# 03_-_MCU_and_Conn.net
KiCad netlist of a schematic drawn in Altium Designer
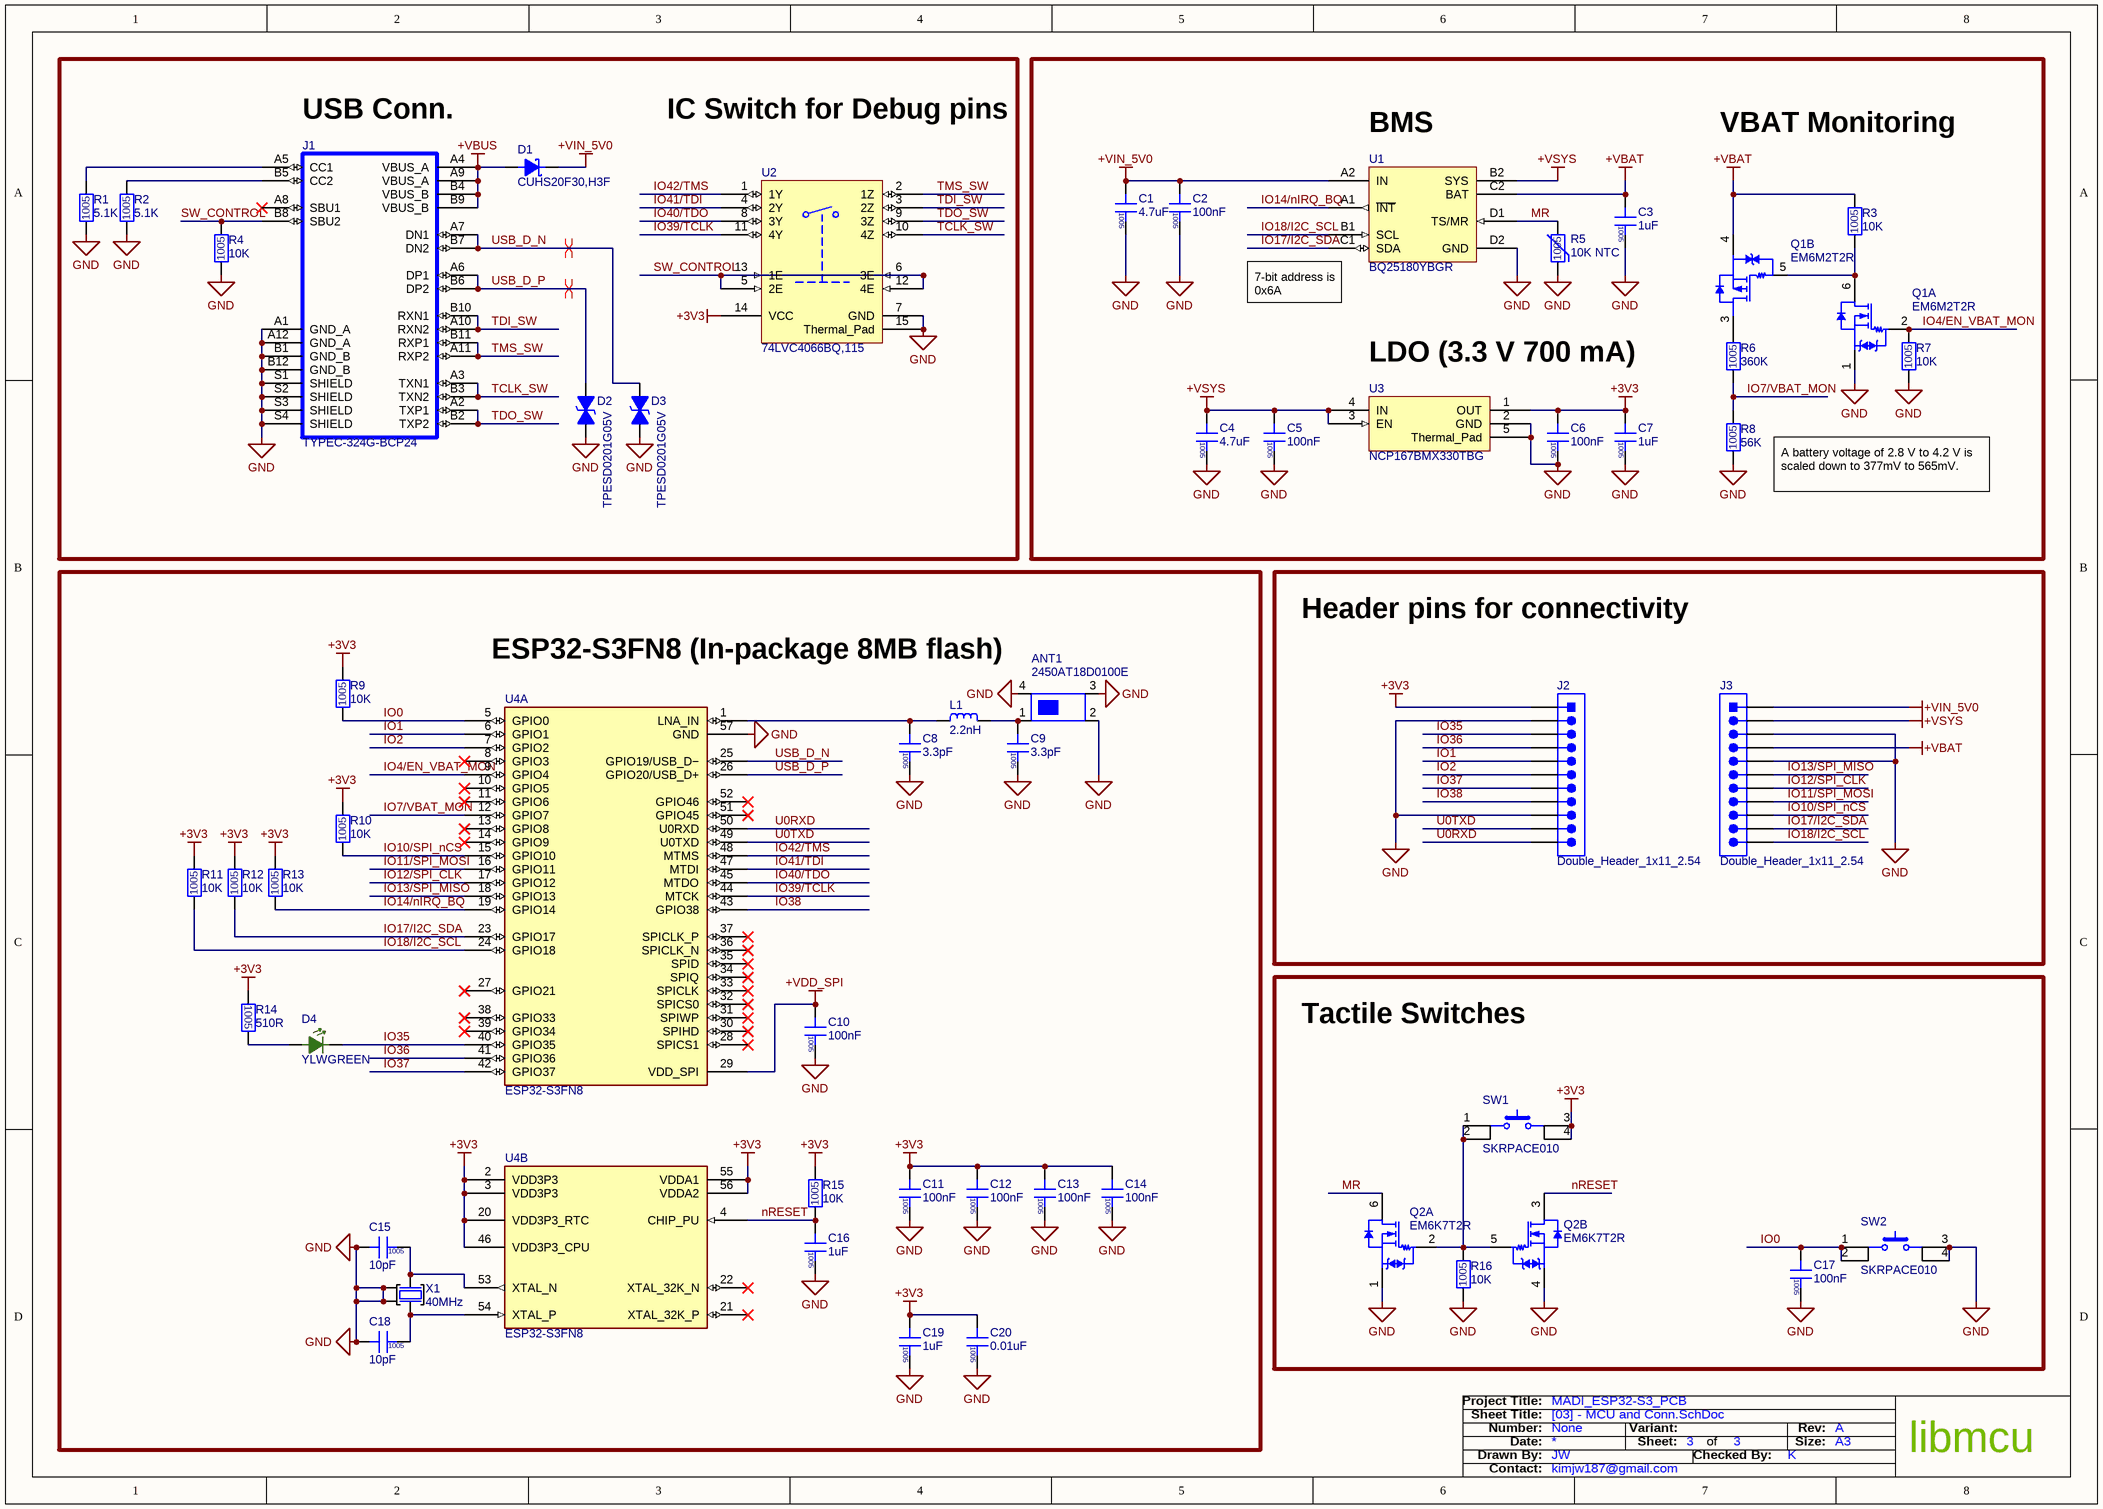
[diagram p0: [03] - MCU and Conn.SchDoc]

(export (version "E")
  (design (tool "Eeschema 10.0.6"))
  (components
    (comp (ref "ANT1")
      (value "2450AT18D0100E")
      (footprint "2450AT18D0100E")
      (description "RF ANT 2.4GHZ CHIP SOLDER SMD")
      (fields (field (name "MANUFACTURER") "Johanson"))
      (libsource (lib "Schlib-master") (part "2450AT18D0100E"))
    )
    (comp (ref "C1")
      (value "4.7uF")
      (footprint "CAPC1005X06N")
      (description "CAP CER 4.7UF 10V X5R 0402")
      (fields
        (field (name "MANUFACTURER") "Samsung")
        (field (name "MANUFACTURER PART NUMBER") "CL05A475MP5NRNC")
      )
      (libsource (lib "Schlib-master") (part "CL05A475MP5NRNC"))
    )
    (comp (ref "C2")
      (value "100nF")
      (footprint "CAPC1005X06N")
      (description "CAP CER 0.1UF 16V X7R 0402")
      (fields
        (field (name "MANUFACTURER") "Samsung")
        (field (name "MANUFACTURER PART NUMBER") "CL05B104KO5NNNC")
      )
      (libsource (lib "Schlib-master") (part "CL05B104KO5NNNC"))
    )
    (comp (ref "C3")
      (value "1uF")
      (footprint "CAPC1005X06N")
      (description "CAP CER 1UF 16V X5R 0402")
      (fields
        (field (name "MANUFACTURER") "Samsung")
        (field (name "MANUFACTURER PART NUMBER") "CL05A105KO5NNNC")
      )
      (libsource (lib "Schlib-master") (part "CL05A105KO5NNNC"))
    )
    (comp (ref "C4")
      (value "4.7uF")
      (footprint "CAPC1005X06N")
      (description "CAP CER 4.7UF 10V X5R 0402")
      (fields
        (field (name "MANUFACTURER") "Samsung")
        (field (name "MANUFACTURER PART NUMBER") "CL05A475MP5NRNC")
      )
      (libsource (lib "Schlib-master") (part "CL05A475MP5NRNC"))
    )
    (comp (ref "C5")
      (value "100nF")
      (footprint "CAPC1005X06N")
      (description "CAP CER 0.1UF 16V X7R 0402")
      (fields
        (field (name "MANUFACTURER") "Samsung")
        (field (name "MANUFACTURER PART NUMBER") "CL05B104KO5NNNC")
      )
      (libsource (lib "Schlib-master") (part "CL05B104KO5NNNC"))
    )
    (comp (ref "C6")
      (value "100nF")
      (footprint "CAPC1005X06N")
      (description "CAP CER 0.1UF 16V X7R 0402")
      (fields
        (field (name "MANUFACTURER") "Samsung")
        (field (name "MANUFACTURER PART NUMBER") "CL05B104KO5NNNC")
      )
      (libsource (lib "Schlib-master") (part "CL05B104KO5NNNC"))
    )
    (comp (ref "C7")
      (value "1uF")
      (footprint "CAPC1005X06N")
      (description "CAP CER 1UF 16V X5R 0402")
      (fields
        (field (name "MANUFACTURER") "Samsung")
        (field (name "MANUFACTURER PART NUMBER") "CL05A105KO5NNNC")
      )
      (libsource (lib "Schlib-master") (part "CL05A105KO5NNNC"))
    )
    (comp (ref "C8")
      (value "3.3pF")
      (footprint "CAPC1005X06N")
      (description "CAP CER 3.3PF 50V C0G/NPO 0402")
      (fields
        (field (name "MANUFACTURER") "Yageo")
        (field (name "MANUFACTURER PART NUMBER") "CC0402CRNPO9BN3R3")
      )
      (libsource (lib "Schlib-master") (part "CC0402CRNPO9BN3R3"))
    )
    (comp (ref "C9")
      (value "3.3pF")
      (footprint "CAPC1005X06N")
      (description "CAP CER 3.3PF 50V C0G/NPO 0402")
      (fields
        (field (name "MANUFACTURER") "Yageo")
        (field (name "MANUFACTURER PART NUMBER") "CC0402CRNPO9BN3R3")
      )
      (libsource (lib "Schlib-master") (part "CC0402CRNPO9BN3R3"))
    )
    (comp (ref "C10")
      (value "100nF")
      (footprint "CAPC1005X06N")
      (description "CAP CER 0.1UF 16V X7R 0402")
      (fields
        (field (name "MANUFACTURER") "Samsung")
        (field (name "MANUFACTURER PART NUMBER") "CL05B104KO5NNNC")
      )
      (libsource (lib "Schlib-master") (part "CL05B104KO5NNNC"))
    )
    (comp (ref "C11")
      (value "100nF")
      (footprint "CAPC1005X06N")
      (description "CAP CER 0.1UF 16V X7R 0402")
      (fields
        (field (name "MANUFACTURER") "Samsung")
        (field (name "MANUFACTURER PART NUMBER") "CL05B104KO5NNNC")
      )
      (libsource (lib "Schlib-master") (part "CL05B104KO5NNNC"))
    )
    (comp (ref "C12")
      (value "100nF")
      (footprint "CAPC1005X06N")
      (description "CAP CER 0.1UF 16V X7R 0402")
      (fields
        (field (name "MANUFACTURER") "Samsung")
        (field (name "MANUFACTURER PART NUMBER") "CL05B104KO5NNNC")
      )
      (libsource (lib "Schlib-master") (part "CL05B104KO5NNNC"))
    )
    (comp (ref "C13")
      (value "100nF")
      (footprint "CAPC1005X06N")
      (description "CAP CER 0.1UF 16V X7R 0402")
      (fields
        (field (name "MANUFACTURER") "Samsung")
        (field (name "MANUFACTURER PART NUMBER") "CL05B104KO5NNNC")
      )
      (libsource (lib "Schlib-master") (part "CL05B104KO5NNNC"))
    )
    (comp (ref "C14")
      (value "100nF")
      (footprint "CAPC1005X06N")
      (description "CAP CER 0.1UF 16V X7R 0402")
      (fields
        (field (name "MANUFACTURER") "Samsung")
        (field (name "MANUFACTURER PART NUMBER") "CL05B104KO5NNNC")
      )
      (libsource (lib "Schlib-master") (part "CL05B104KO5NNNC"))
    )
    (comp (ref "C15")
      (value "10pF")
      (footprint "CAPC1005X06N")
      (description "CAP CER 10PF 50V C0G/NPO 0402")
      (fields
        (field (name "MANUFACTURER") "Yageo")
        (field (name "MANUFACTURER PART NUMBER") "CC0402JRNPO9BN100")
      )
      (libsource (lib "Schlib-master") (part "CC0402JRNPO9BN100"))
    )
    (comp (ref "C16")
      (value "1uF")
      (footprint "CAPC1005X06N")
      (description "CAP CER 1UF 16V X5R 0402")
      (fields
        (field (name "MANUFACTURER") "Samsung")
        (field (name "MANUFACTURER PART NUMBER") "CL05A105KO5NNNC")
      )
      (libsource (lib "Schlib-master") (part "CL05A105KO5NNNC"))
    )
    (comp (ref "C17")
      (value "100nF")
      (footprint "CAPC1005X06N")
      (description "CAP CER 0.1UF 16V X7R 0402")
      (fields
        (field (name "MANUFACTURER") "Samsung")
        (field (name "MANUFACTURER PART NUMBER") "CL05B104KO5NNNC")
      )
      (libsource (lib "Schlib-master") (part "CL05B104KO5NNNC"))
    )
    (comp (ref "C18")
      (value "10pF")
      (footprint "CAPC1005X06N")
      (description "CAP CER 10PF 50V C0G/NPO 0402")
      (fields
        (field (name "MANUFACTURER") "Yageo")
        (field (name "MANUFACTURER PART NUMBER") "CC0402JRNPO9BN100")
      )
      (libsource (lib "Schlib-master") (part "CC0402JRNPO9BN100"))
    )
    (comp (ref "C19")
      (value "1uF")
      (footprint "CAPC1005X06N")
      (description "CAP CER 1UF 16V X5R 0402")
      (fields
        (field (name "MANUFACTURER") "Samsung")
        (field (name "MANUFACTURER PART NUMBER") "CL05A105KO5NNNC")
      )
      (libsource (lib "Schlib-master") (part "CL05A105KO5NNNC"))
    )
    (comp (ref "C20")
      (value "0.01uF")
      (footprint "CAPC1005X06N")
      (description "CAP CER 10000PF 25V X7R 0402")
      (fields
        (field (name "MANUFACTURER") "Samsung")
        (field (name "MANUFACTURER PART NUMBER") "CL05B103KA5NNNC")
      )
      (libsource (lib "Schlib-master") (part "CL05B103KA5NNNC"))
    )
    (comp (ref "D1")
      (value "CUHS20F30,H3F")
      (footprint "US2H-DIODE")
      (description "DIODE SCHOTTKY 30V 2A US2H")
      (fields (field (name "MANUFACTURER") "Toshiba"))
      (libsource (lib "Schlib-master") (part "CUHS20F30,H3F"))
    )
    (comp (ref "D2")
      (value "TPESD0201G05V")
      (footprint "DIOC0603X03N")
      (description "TVS DIODE 5.5VWM 40VC 0201")
      (fields (field (name "MANUFACTURER") "TECH PUBLIC"))
      (libsource (lib "Schlib-master") (part "TPESD0201G05V"))
    )
    (comp (ref "D3")
      (value "TPESD0201G05V")
      (footprint "DIOC0603X03N")
      (description "TVS DIODE 5.5VWM 40VC 0201")
      (fields (field (name "MANUFACTURER") "TECH PUBLIC"))
      (libsource (lib "Schlib-master") (part "TPESD0201G05V"))
    )
    (comp (ref "D4")
      (value "YLWGREEN")
      (footprint "LDIOC1608X08N")
      (description "LED YLW/GREEN DIFFUSED 1608 SMD")
      (fields
        (field (name "MANUFACTURER") "Everlight")
        (field (name "MANUFACTURER PART NUMBER") "19-217/G7C-AN1P2/3T")
      )
      (libsource (lib "Schlib-master") (part "19-217/G7C-AN1P2/3T"))
    )
    (comp (ref "J1")
      (value "TYPEC-324G-BCP24")
      (footprint "KUSBX-SMT3-CS-BTR_KYC")
      (description "CONN RCPT USB TYPE C, SMT PINS, TH SHIELD")
      (fields (field (name "MANUFACTURER") "XUNPU"))
      (libsource (lib "Schlib-master") (part "TYPEC-324G-BCP24"))
    )
    (comp (ref "J2")
      (value "Double_Header_1x11_2.54")
      (footprint "1x11_DOUBLE_HEADER_2.54")
      (libsource (lib "") (part "Double_Header_1x11_2.54_1"))
    )
    (comp (ref "J3")
      (value "Double_Header_1x11_2.54")
      (footprint "1x11_DOUBLE_HEADER_2.54")
      (libsource (lib "Schlib-master") (part "Double_Header_1x11_2.54"))
    )
    (comp (ref "L1")
      (value "2.2nH")
      (footprint "INDC1005X05N")
      (description "FIXED IND 2.2NH 400MA 180 MOHM")
      (fields
        (field (name "MANUFACTURER") "Chilisin Elec")
        (field (name "MANUFACTURER PART NUMBER") "CLH1005T-2N2S-S-NP")
      )
      (libsource (lib "Schlib-master") (part "CLH1005T-2N2S-S-NP"))
    )
    (comp (ref "Q1")
      (value "EM6M2T2R")
      (footprint "SOTFL50P160X55-6N")
      (description "MOSFET N/P-CH 20V 0.2A EMT6")
      (fields (field (name "MANUFACTURER") "Rohm"))
      (libsource (lib "Schlib-master") (part "EM6M2T2R"))
    )
    (comp (ref "Q2")
      (value "EM6K7T2R")
      (footprint "SOTFL50P160X55-6N")
      (description "MOSFET 2N-CH 20V 0.2A EMT6")
      (fields (field (name "MANUFACTURER") "Rohm"))
      (libsource (lib "Schlib-master") (part "EM6K7T2R"))
    )
    (comp (ref "R1")
      (value "5.1K")
      (footprint "RESC1005X04N")
      (description "RES SMD 5.1K OHM 1% 1/16W 0402")
      (fields
        (field (name "MANUFACTURER") "Yageo")
        (field (name "MANUFACTURER PART NUMBER") "RC0402FR-075K1L")
      )
      (libsource (lib "Schlib-master") (part "RC0402FR-075K1L"))
    )
    (comp (ref "R2")
      (value "5.1K")
      (footprint "RESC1005X04N")
      (description "RES SMD 5.1K OHM 1% 1/16W 0402")
      (fields
        (field (name "MANUFACTURER") "Yageo")
        (field (name "MANUFACTURER PART NUMBER") "RC0402FR-075K1L")
      )
      (libsource (lib "Schlib-master") (part "RC0402FR-075K1L"))
    )
    (comp (ref "R3")
      (value "10K")
      (footprint "RESC1005X04N")
      (description "RES SMD 10K OHM 1% 1/16W 0402")
      (fields
        (field (name "MANUFACTURER") "Yageo")
        (field (name "MANUFACTURER PART NUMBER") "RC0402FR-0710KL")
      )
      (libsource (lib "Schlib-master") (part "RC0402FR-0710KL"))
    )
    (comp (ref "R4")
      (value "10K")
      (footprint "RESC1005X04N")
      (description "RES SMD 10K OHM 1% 1/16W 0402")
      (fields
        (field (name "MANUFACTURER") "Yageo")
        (field (name "MANUFACTURER PART NUMBER") "RC0402FR-0710KL")
      )
      (libsource (lib "Schlib-master") (part "RC0402FR-0710KL"))
    )
    (comp (ref "R5")
      (value "10K NTC")
      (footprint "NTC1005X05N")
      (description "THERMISTOR NTC 10KOHM 3380K 0402")
      (fields
        (field (name "MANUFACTURER") "Murata")
        (field (name "MANUFACTURER PART NUMBER") "NCP15XH103F03RC")
      )
      (libsource (lib "Schlib-master") (part "NCP15XH103F03RC"))
    )
    (comp (ref "R6")
      (value "360K")
      (footprint "RESC1005X04N")
      (description "RES SMD 360K OHM 1% 1/16W 0402")
      (fields
        (field (name "MANUFACTURER") "Yageo")
        (field (name "MANUFACTURER PART NUMBER") "RC0402FR-07360KL")
      )
      (libsource (lib "Schlib-master") (part "RC0402FR-07360KL"))
    )
    (comp (ref "R7")
      (value "10K")
      (footprint "RESC1005X04N")
      (description "RES SMD 10K OHM 1% 1/16W 0402")
      (fields
        (field (name "MANUFACTURER") "Yageo")
        (field (name "MANUFACTURER PART NUMBER") "RC0402FR-0710KL")
      )
      (libsource (lib "Schlib-master") (part "RC0402FR-0710KL"))
    )
    (comp (ref "R8")
      (value "56K")
      (footprint "RESC1005X04N")
      (description "RES SMD 56K OHM 1% 1/16W 0402")
      (fields
        (field (name "MANUFACTURER") "Yageo")
        (field (name "MANUFACTURER PART NUMBER") "RC0402FR-0756KL")
      )
      (libsource (lib "Schlib-master") (part "RC0402FR-0756KL"))
    )
    (comp (ref "R9")
      (value "10K")
      (footprint "RESC1005X04N")
      (description "RES SMD 10K OHM 1% 1/16W 0402")
      (fields
        (field (name "MANUFACTURER") "Yageo")
        (field (name "MANUFACTURER PART NUMBER") "RC0402FR-0710KL")
      )
      (libsource (lib "Schlib-master") (part "RC0402FR-0710KL"))
    )
    (comp (ref "R10")
      (value "10K")
      (footprint "RESC1005X04N")
      (description "RES SMD 10K OHM 1% 1/16W 0402")
      (fields
        (field (name "MANUFACTURER") "Yageo")
        (field (name "MANUFACTURER PART NUMBER") "RC0402FR-0710KL")
      )
      (libsource (lib "Schlib-master") (part "RC0402FR-0710KL"))
    )
    (comp (ref "R11")
      (value "10K")
      (footprint "RESC1005X04N")
      (description "RES SMD 10K OHM 1% 1/16W 0402")
      (fields
        (field (name "MANUFACTURER") "Yageo")
        (field (name "MANUFACTURER PART NUMBER") "RC0402FR-0710KL")
      )
      (libsource (lib "Schlib-master") (part "RC0402FR-0710KL"))
    )
    (comp (ref "R12")
      (value "10K")
      (footprint "RESC1005X04N")
      (description "RES SMD 10K OHM 1% 1/16W 0402")
      (fields
        (field (name "MANUFACTURER") "Yageo")
        (field (name "MANUFACTURER PART NUMBER") "RC0402FR-0710KL")
      )
      (libsource (lib "Schlib-master") (part "RC0402FR-0710KL"))
    )
    (comp (ref "R13")
      (value "10K")
      (footprint "RESC1005X04N")
      (description "RES SMD 10K OHM 1% 1/16W 0402")
      (fields
        (field (name "MANUFACTURER") "Yageo")
        (field (name "MANUFACTURER PART NUMBER") "RC0402FR-0710KL")
      )
      (libsource (lib "Schlib-master") (part "RC0402FR-0710KL"))
    )
    (comp (ref "R14")
      (value "510R")
      (footprint "RESC1005X04N")
      (description "RES SMD 510 OHM 1% 1/16W 0402")
      (fields (field (name "TOLERANCE") "1%") (field (name "MANUFACTURER") "Yageo"))
      (libsource (lib "Schlib-master") (part "RC0402FR-07510RL"))
    )
    (comp (ref "R15")
      (value "10K")
      (footprint "RESC1005X04N")
      (description "RES SMD 10K OHM 1% 1/16W 0402")
      (fields
        (field (name "MANUFACTURER") "Yageo")
        (field (name "MANUFACTURER PART NUMBER") "RC0402FR-0710KL")
      )
      (libsource (lib "Schlib-master") (part "RC0402FR-0710KL"))
    )
    (comp (ref "R16")
      (value "10K")
      (footprint "RESC1005X04N")
      (description "RES SMD 10K OHM 1% 1/16W 0402")
      (fields
        (field (name "MANUFACTURER") "Yageo")
        (field (name "MANUFACTURER PART NUMBER") "RC0402FR-0710KL")
      )
      (libsource (lib "Schlib-master") (part "RC0402FR-0710KL"))
    )
    (comp (ref "SW1")
      (value "SKRPACE010")
      (footprint "PTS810")
      (description "SWITCH TACTILE SPST-NO 0.05A 16V")
      (fields (field (name "MANUFACTURER") "Alps Electric"))
      (libsource (lib "Schlib-master") (part "SKRPACE010"))
    )
    (comp (ref "SW2")
      (value "SKRPACE010")
      (footprint "PTS810")
      (description "SWITCH TACTILE SPST-NO 0.05A 16V")
      (fields (field (name "MANUFACTURER") "Alps Electric"))
      (libsource (lib "Schlib-master") (part "SKRPACE010"))
    )
    (comp (ref "U1")
      (value "BQ25180YBGR")
      (footprint "BGA8C40P2X4_100X155X50_YBG0008")
      (description "IC 1-A LI-ION IC PROGRAMMABLE CHARG")
      (fields (field (name "MANUFACTURER") "Texas Instruments"))
      (libsource (lib "Schlib-master") (part "BQ25180YBGR"))
    )
    (comp (ref "U2")
      (value "74LVC4066BQ,115")
      (footprint "QFN50P250X300X100_HS-15N")
      (description "IC SWITCH QUAD SPST 14DHVQFN")
      (fields (field (name "MANUFACTURER") "Nexperia"))
      (libsource (lib "Schlib-master") (part "74LVC4066BQ,115"))
    )
    (comp (ref "U3")
      (value "NCP167BMX330TBG")
      (footprint "NCP167")
      (description "IC REG LINEAR 3.3V 700MA 4XDFN")
      (fields (field (name "MANUFACTURER") "ON Semiconductor"))
      (libsource (lib "Schlib-master") (part "NCP167BMX330TBG"))
    )
    (comp (ref "U4")
      (value "ESP32-S3FN8")
      (footprint "QFN40P700X700X90_HS-57N")
      (description "IC RF TXRX+MCU BLUETOOTH WIFI")
      (fields (field (name "MANUFACTURER") "Espressif Systems"))
      (libsource (lib "Schlib-master") (part "ESP32-S3FN8"))
    )
    (comp (ref "X1")
      (value "40MHz")
      (footprint "XT2016_ECS")
      (description "CRYSTAL 40.0000MHZ 9PF SMD")
      (fields (field (name "MANUFACTURER") "HD") (field (name "MANUFACTURER PART NUMBER") "7D040000H01"))
      (libsource (lib "Schlib-master") (part "7D040000H01"))
    )
  )
  (nets
    (net (code "1") (name "+3V3") (class "Default")
      (node (ref "C11") (pin "2") (pinfunction "2_2") (pintype "passive"))
      (node (ref "C12") (pin "2") (pinfunction "2_2") (pintype "passive"))
      (node (ref "C13") (pin "2") (pinfunction "2_2") (pintype "passive"))
      (node (ref "C14") (pin "2") (pinfunction "2_2") (pintype "passive"))
      (node (ref "C19") (pin "2") (pinfunction "2_2") (pintype "passive"))
      (node (ref "C20") (pin "2") (pinfunction "2_2") (pintype "passive"))
      (node (ref "C6") (pin "2") (pinfunction "2_2") (pintype "passive"))
      (node (ref "C7") (pin "2") (pinfunction "2_2") (pintype "passive"))
      (node (ref "J2") (pin "1") (pinfunction "1_1") (pintype "passive"))
      (node (ref "R10") (pin "2") (pinfunction "2_2") (pintype "passive"))
      (node (ref "R11") (pin "2") (pinfunction "2_2") (pintype "passive"))
      (node (ref "R12") (pin "2") (pinfunction "2_2") (pintype "passive"))
      (node (ref "R13") (pin "2") (pinfunction "2_2") (pintype "passive"))
      (node (ref "R14") (pin "2") (pinfunction "2_2") (pintype "passive"))
      (node (ref "R15") (pin "2") (pinfunction "2_2") (pintype "passive"))
      (node (ref "R9") (pin "2") (pinfunction "2_2") (pintype "passive"))
      (node (ref "SW1") (pin "3") (pinfunction "2_3") (pintype "passive"))
      (node (ref "SW1") (pin "4") (pinfunction "1_4") (pintype "passive"))
      (node (ref "U2") (pin "14") (pinfunction "VCC_14") (pintype "power_in"))
      (node (ref "U3") (pin "1") (pinfunction "OUT_1") (pintype "power_in"))
      (node (ref "U4") (pin "2") (pinfunction "VDD3P3_2") (pintype "power_in"))
      (node (ref "U4") (pin "20") (pinfunction "VDD3P3_RTC_20") (pintype "power_in"))
      (node (ref "U4") (pin "3") (pinfunction "VDD3P3_3") (pintype "power_in"))
      (node (ref "U4") (pin "46") (pinfunction "VDD3P3_CPU_46") (pintype "power_in"))
      (node (ref "U4") (pin "55") (pinfunction "VDDA1_55") (pintype "power_in"))
      (node (ref "U4") (pin "56") (pinfunction "VDDA2_56") (pintype "power_in"))
    )
    (net (code "2") (name "+VBAT") (class "Default")
      (node (ref "C3") (pin "2") (pinfunction "2_2") (pintype "passive"))
      (node (ref "J3") (pin "4") (pinfunction "4_4") (pintype "passive"))
      (node (ref "Q1") (pin "4") (pinfunction "S_4") (pintype "passive"))
      (node (ref "R3") (pin "2") (pinfunction "2_2") (pintype "passive"))
      (node (ref "U1") (pin "C2") (pinfunction "BAT_C2") (pintype "power_in"))
    )
    (net (code "3") (name "+VBUS") (class "Default")
      (node (ref "D1") (pin "2") (pinfunction "Anode_2") (pintype "passive"))
      (node (ref "J1") (pin "A4") (pinfunction "VBUS_A_A4") (pintype "power_in"))
      (node (ref "J1") (pin "A9") (pinfunction "VBUS_A_A9") (pintype "power_in"))
      (node (ref "J1") (pin "B4") (pinfunction "VBUS_B_B4") (pintype "power_in"))
      (node (ref "J1") (pin "B9") (pinfunction "VBUS_B_B9") (pintype "power_in"))
    )
    (net (code "4") (name "+VDD_SPI") (class "Default")
      (node (ref "C10") (pin "2") (pinfunction "2_2") (pintype "passive"))
      (node (ref "U4") (pin "29") (pinfunction "VDD_SPI_29") (pintype "power_in"))
    )
    (net (code "5") (name "+VIN_5V0") (class "Default")
      (node (ref "C1") (pin "2") (pinfunction "2_2") (pintype "passive"))
      (node (ref "C2") (pin "2") (pinfunction "2_2") (pintype "passive"))
      (node (ref "D1") (pin "1") (pinfunction "Cathode_1") (pintype "passive"))
      (node (ref "J3") (pin "1") (pinfunction "1_1") (pintype "passive"))
      (node (ref "U1") (pin "A2") (pinfunction "IN_A2") (pintype "power_in"))
    )
    (net (code "6") (name "+VSYS") (class "Default")
      (node (ref "C4") (pin "2") (pinfunction "2_2") (pintype "passive"))
      (node (ref "C5") (pin "2") (pinfunction "2_2") (pintype "passive"))
      (node (ref "J3") (pin "2") (pinfunction "2_2") (pintype "passive"))
      (node (ref "U1") (pin "B2") (pinfunction "SYS_B2") (pintype "power_in"))
      (node (ref "U3") (pin "3") (pinfunction "EN_3") (pintype "input"))
      (node (ref "U3") (pin "4") (pinfunction "IN_4") (pintype "power_in"))
    )
    (net (code "7") (name "/IO0") (class "Default")
      (node (ref "C17") (pin "2") (pinfunction "2_2") (pintype "passive"))
      (node (ref "R9") (pin "1") (pinfunction "1_1") (pintype "passive"))
      (node (ref "SW2") (pin "1") (pinfunction "1_1") (pintype "passive"))
      (node (ref "SW2") (pin "2") (pinfunction "2_2") (pintype "passive"))
      (node (ref "U4") (pin "5") (pinfunction "GPIO0_5") (pintype "bidirectional"))
    )
    (net (code "8") (name "/IO1") (class "Default")
      (node (ref "J2") (pin "5") (pinfunction "5_5") (pintype "passive"))
      (node (ref "U4") (pin "6") (pinfunction "GPIO1_6") (pintype "bidirectional"))
    )
    (net (code "9") (name "/IO2") (class "Default")
      (node (ref "J2") (pin "6") (pinfunction "6_6") (pintype "passive"))
      (node (ref "U4") (pin "7") (pinfunction "GPIO2_7") (pintype "bidirectional"))
    )
    (net (code "10") (name "/IO4{slash}EN_VBAT_MON") (class "Default")
      (node (ref "Q1") (pin "2") (pinfunction "G_2") (pintype "passive"))
      (node (ref "R7") (pin "2") (pinfunction "2_2") (pintype "passive"))
      (node (ref "U4") (pin "9") (pinfunction "GPIO4_9") (pintype "bidirectional"))
    )
    (net (code "11") (name "/IO7{slash}VBAT_MON") (class "Default")
      (node (ref "R6") (pin "1") (pinfunction "1_1") (pintype "passive"))
      (node (ref "R8") (pin "2") (pinfunction "2_2") (pintype "passive"))
      (node (ref "U4") (pin "12") (pinfunction "GPIO7_12") (pintype "bidirectional"))
    )
    (net (code "12") (name "/IO10{slash}SPI_nCS") (class "Default")
      (node (ref "J3") (pin "9") (pinfunction "9_9") (pintype "passive"))
      (node (ref "R10") (pin "1") (pinfunction "1_1") (pintype "passive"))
      (node (ref "U4") (pin "15") (pinfunction "GPIO10_15") (pintype "bidirectional"))
    )
    (net (code "13") (name "/IO11{slash}SPI_MOSI") (class "Default")
      (node (ref "J3") (pin "8") (pinfunction "8_8") (pintype "passive"))
      (node (ref "U4") (pin "16") (pinfunction "GPIO11_16") (pintype "bidirectional"))
    )
    (net (code "14") (name "/IO12{slash}SPI_CLK") (class "Default")
      (node (ref "J3") (pin "7") (pinfunction "7_7") (pintype "passive"))
      (node (ref "U4") (pin "17") (pinfunction "GPIO12_17") (pintype "bidirectional"))
    )
    (net (code "15") (name "/IO13{slash}SPI_MISO") (class "Default")
      (node (ref "J3") (pin "6") (pinfunction "6_6") (pintype "passive"))
      (node (ref "U4") (pin "18") (pinfunction "GPIO13_18") (pintype "bidirectional"))
    )
    (net (code "16") (name "/IO14{slash}nIRQ_BQ") (class "Default")
      (node (ref "R13") (pin "1") (pinfunction "1_1") (pintype "passive"))
      (node (ref "U1") (pin "A1") (pinfunction "~{INT}_A1") (pintype "output"))
      (node (ref "U4") (pin "19") (pinfunction "GPIO14_19") (pintype "bidirectional"))
    )
    (net (code "17") (name "/IO17{slash}I2C_SDA") (class "Default")
      (node (ref "J3") (pin "10") (pinfunction "10_10") (pintype "passive"))
      (node (ref "R12") (pin "1") (pinfunction "1_1") (pintype "passive"))
      (node (ref "U1") (pin "C1") (pinfunction "SDA_C1") (pintype "bidirectional"))
      (node (ref "U4") (pin "23") (pinfunction "GPIO17_23") (pintype "bidirectional"))
    )
    (net (code "18") (name "/IO18{slash}I2C_SCL") (class "Default")
      (node (ref "J3") (pin "11") (pinfunction "11_11") (pintype "passive"))
      (node (ref "R11") (pin "1") (pinfunction "1_1") (pintype "passive"))
      (node (ref "U1") (pin "B1") (pinfunction "SCL_B1") (pintype "input"))
      (node (ref "U4") (pin "24") (pinfunction "GPIO18_24") (pintype "bidirectional"))
    )
    (net (code "19") (name "/IO35") (class "Default")
      (node (ref "D4") (pin "K") (pinfunction "2_K") (pintype "passive"))
      (node (ref "J2") (pin "3") (pinfunction "3_3") (pintype "passive"))
      (node (ref "U4") (pin "40") (pinfunction "GPIO35_40") (pintype "bidirectional"))
    )
    (net (code "20") (name "/IO36") (class "Default")
      (node (ref "J2") (pin "4") (pinfunction "4_4") (pintype "passive"))
      (node (ref "U4") (pin "41") (pinfunction "GPIO36_41") (pintype "bidirectional"))
    )
    (net (code "21") (name "/IO37") (class "Default")
      (node (ref "J2") (pin "7") (pinfunction "7_7") (pintype "passive"))
      (node (ref "U4") (pin "42") (pinfunction "GPIO37_42") (pintype "bidirectional"))
    )
    (net (code "22") (name "/IO38") (class "Default")
      (node (ref "J2") (pin "8") (pinfunction "8_8") (pintype "passive"))
      (node (ref "U4") (pin "43") (pinfunction "GPIO38_43") (pintype "bidirectional"))
    )
    (net (code "23") (name "/IO39{slash}TCLK") (class "Default")
      (node (ref "U2") (pin "11") (pinfunction "4Y_11") (pintype "bidirectional"))
      (node (ref "U4") (pin "44") (pinfunction "MTCK_44") (pintype "bidirectional"))
    )
    (net (code "24") (name "/IO40{slash}TDO") (class "Default")
      (node (ref "U2") (pin "8") (pinfunction "3Y_8") (pintype "bidirectional"))
      (node (ref "U4") (pin "45") (pinfunction "MTDO_45") (pintype "bidirectional"))
    )
    (net (code "25") (name "/IO41{slash}TDI") (class "Default")
      (node (ref "U2") (pin "4") (pinfunction "2Y_4") (pintype "bidirectional"))
      (node (ref "U4") (pin "47") (pinfunction "MTDI_47") (pintype "bidirectional"))
    )
    (net (code "26") (name "/IO42{slash}TMS") (class "Default")
      (node (ref "U2") (pin "1") (pinfunction "1Y_1") (pintype "bidirectional"))
      (node (ref "U4") (pin "48") (pinfunction "MTMS_48") (pintype "bidirectional"))
    )
    (net (code "27") (name "/MR") (class "Default")
      (node (ref "Q2") (pin "6") (pinfunction "D_6") (pintype "passive"))
      (node (ref "R5") (pin "2") (pinfunction "2_2") (pintype "passive"))
      (node (ref "U1") (pin "D1") (pinfunction "TS/MR_D1") (pintype "input"))
    )
    (net (code "28") (name "/SW_CONTROL") (class "Default")
      (node (ref "J1") (pin "B8") (pinfunction "SBU2_B8") (pintype "bidirectional"))
      (node (ref "R4") (pin "2") (pinfunction "2_2") (pintype "passive"))
      (node (ref "U2") (pin "12") (pinfunction "4E_12") (pintype "input"))
      (node (ref "U2") (pin "13") (pinfunction "1E_13") (pintype "input"))
      (node (ref "U2") (pin "5") (pinfunction "2E_5") (pintype "input"))
      (node (ref "U2") (pin "6") (pinfunction "3E_6") (pintype "input"))
    )
    (net (code "29") (name "/TCLK_SW") (class "Default")
      (node (ref "J1") (pin "A3") (pinfunction "TXN1_A3") (pintype "bidirectional"))
      (node (ref "J1") (pin "B3") (pinfunction "TXN2_B3") (pintype "bidirectional"))
      (node (ref "U2") (pin "10") (pinfunction "4Z_10") (pintype "bidirectional"))
    )
    (net (code "30") (name "/TDI_SW") (class "Default")
      (node (ref "J1") (pin "A10") (pinfunction "RXN2_A10") (pintype "bidirectional"))
      (node (ref "J1") (pin "B10") (pinfunction "RXN1_B10") (pintype "bidirectional"))
      (node (ref "U2") (pin "3") (pinfunction "2Z_3") (pintype "bidirectional"))
    )
    (net (code "31") (name "/TDO_SW") (class "Default")
      (node (ref "J1") (pin "A2") (pinfunction "TXP1_A2") (pintype "bidirectional"))
      (node (ref "J1") (pin "B2") (pinfunction "TXP2_B2") (pintype "bidirectional"))
      (node (ref "U2") (pin "9") (pinfunction "3Z_9") (pintype "bidirectional"))
    )
    (net (code "32") (name "/TMS_SW") (class "Default")
      (node (ref "J1") (pin "A11") (pinfunction "RXP2_A11") (pintype "bidirectional"))
      (node (ref "J1") (pin "B11") (pinfunction "RXP1_B11") (pintype "bidirectional"))
      (node (ref "U2") (pin "2") (pinfunction "1Z_2") (pintype "bidirectional"))
    )
    (net (code "33") (name "/U0RXD") (class "Default")
      (node (ref "J2") (pin "11") (pinfunction "11_11") (pintype "passive"))
      (node (ref "U4") (pin "50") (pinfunction "U0RXD_50") (pintype "bidirectional"))
    )
    (net (code "34") (name "/U0TXD") (class "Default")
      (node (ref "J2") (pin "10") (pinfunction "10_10") (pintype "passive"))
      (node (ref "U4") (pin "49") (pinfunction "U0TXD_49") (pintype "bidirectional"))
    )
    (net (code "35") (name "/USB_D_N") (class "Default")
      (node (ref "D3") (pin "1") (pinfunction "1_1") (pintype "passive"))
      (node (ref "J1") (pin "A7") (pinfunction "DN1_A7") (pintype "bidirectional"))
      (node (ref "J1") (pin "B7") (pinfunction "DN2_B7") (pintype "bidirectional"))
      (node (ref "U4") (pin "25") (pinfunction "GPIO19/USB_D−_25") (pintype "bidirectional"))
    )
    (net (code "36") (name "/USB_D_P") (class "Default")
      (node (ref "D2") (pin "1") (pinfunction "1_1") (pintype "passive"))
      (node (ref "J1") (pin "A6") (pinfunction "DP1_A6") (pintype "bidirectional"))
      (node (ref "J1") (pin "B6") (pinfunction "DP2_B6") (pintype "bidirectional"))
      (node (ref "U4") (pin "26") (pinfunction "GPIO20/USB_D+_26") (pintype "bidirectional"))
    )
    (net (code "37") (name "/nRESET") (class "Default")
      (node (ref "C16") (pin "2") (pinfunction "2_2") (pintype "passive"))
      (node (ref "Q2") (pin "3") (pinfunction "D_3") (pintype "passive"))
      (node (ref "R15") (pin "1") (pinfunction "1_1") (pintype "passive"))
      (node (ref "U4") (pin "4") (pinfunction "CHIP_PU_4") (pintype "input"))
    )
    (net (code "38") (name "GND") (class "Default")
      (node (ref "ANT1") (pin "2") (pinfunction "GND_2") (pintype "passive"))
      (node (ref "ANT1") (pin "3") (pinfunction "GND_3") (pintype "passive"))
      (node (ref "ANT1") (pin "4") (pinfunction "GND_4") (pintype "passive"))
      (node (ref "C1") (pin "1") (pinfunction "1_1") (pintype "passive"))
      (node (ref "C10") (pin "1") (pinfunction "1_1") (pintype "passive"))
      (node (ref "C11") (pin "1") (pinfunction "1_1") (pintype "passive"))
      (node (ref "C12") (pin "1") (pinfunction "1_1") (pintype "passive"))
      (node (ref "C13") (pin "1") (pinfunction "1_1") (pintype "passive"))
      (node (ref "C14") (pin "1") (pinfunction "1_1") (pintype "passive"))
      (node (ref "C15") (pin "2") (pinfunction "2_2") (pintype "passive"))
      (node (ref "C16") (pin "1") (pinfunction "1_1") (pintype "passive"))
      (node (ref "C17") (pin "1") (pinfunction "1_1") (pintype "passive"))
      (node (ref "C18") (pin "2") (pinfunction "2_2") (pintype "passive"))
      (node (ref "C19") (pin "1") (pinfunction "1_1") (pintype "passive"))
      (node (ref "C2") (pin "1") (pinfunction "1_1") (pintype "passive"))
      (node (ref "C20") (pin "1") (pinfunction "1_1") (pintype "passive"))
      (node (ref "C3") (pin "1") (pinfunction "1_1") (pintype "passive"))
      (node (ref "C4") (pin "1") (pinfunction "1_1") (pintype "passive"))
      (node (ref "C5") (pin "1") (pinfunction "1_1") (pintype "passive"))
      (node (ref "C6") (pin "1") (pinfunction "1_1") (pintype "passive"))
      (node (ref "C7") (pin "1") (pinfunction "1_1") (pintype "passive"))
      (node (ref "C8") (pin "1") (pinfunction "1_1") (pintype "passive"))
      (node (ref "C9") (pin "1") (pinfunction "1_1") (pintype "passive"))
      (node (ref "D2") (pin "2") (pinfunction "2_2") (pintype "passive"))
      (node (ref "D3") (pin "2") (pinfunction "2_2") (pintype "passive"))
      (node (ref "J1") (pin "A1") (pinfunction "GND_A_A1") (pintype "power_in"))
      (node (ref "J1") (pin "A12") (pinfunction "GND_A_A12") (pintype "power_in"))
      (node (ref "J1") (pin "B1") (pinfunction "GND_B_B1") (pintype "power_in"))
      (node (ref "J1") (pin "B12") (pinfunction "GND_B_B12") (pintype "power_in"))
      (node (ref "J1") (pin "S1") (pinfunction "SHIELD_S1") (pintype "passive"))
      (node (ref "J1") (pin "S2") (pinfunction "SHIELD_S2") (pintype "passive"))
      (node (ref "J1") (pin "S3") (pinfunction "SHIELD_S3") (pintype "passive"))
      (node (ref "J1") (pin "S4") (pinfunction "SHIELD_S4") (pintype "passive"))
      (node (ref "J2") (pin "2") (pinfunction "2_2") (pintype "passive"))
      (node (ref "J2") (pin "9") (pinfunction "9_9") (pintype "passive"))
      (node (ref "J3") (pin "3") (pinfunction "3_3") (pintype "passive"))
      (node (ref "J3") (pin "5") (pinfunction "5_5") (pintype "passive"))
      (node (ref "Q1") (pin "1") (pinfunction "S_1") (pintype "passive"))
      (node (ref "Q2") (pin "1") (pinfunction "S_1") (pintype "passive"))
      (node (ref "Q2") (pin "4") (pinfunction "S_4") (pintype "passive"))
      (node (ref "R1") (pin "1") (pinfunction "1_1") (pintype "passive"))
      (node (ref "R16") (pin "1") (pinfunction "1_1") (pintype "passive"))
      (node (ref "R2") (pin "1") (pinfunction "1_1") (pintype "passive"))
      (node (ref "R4") (pin "1") (pinfunction "1_1") (pintype "passive"))
      (node (ref "R5") (pin "1") (pinfunction "1_1") (pintype "passive"))
      (node (ref "R7") (pin "1") (pinfunction "1_1") (pintype "passive"))
      (node (ref "R8") (pin "1") (pinfunction "1_1") (pintype "passive"))
      (node (ref "SW2") (pin "3") (pinfunction "2_3") (pintype "passive"))
      (node (ref "SW2") (pin "4") (pinfunction "1_4") (pintype "passive"))
      (node (ref "U1") (pin "D2") (pinfunction "GND_D2") (pintype "power_in"))
      (node (ref "U2") (pin "15") (pinfunction "Thermal_Pad_15") (pintype "power_in"))
      (node (ref "U2") (pin "7") (pinfunction "GND_7") (pintype "power_in"))
      (node (ref "U3") (pin "2") (pinfunction "GND_2") (pintype "power_in"))
      (node (ref "U3") (pin "5") (pinfunction "Thermal_Pad_5") (pintype "passive"))
      (node (ref "U4") (pin "57") (pinfunction "GND_57") (pintype "power_in"))
      (node (ref "X1") (pin "2") (pinfunction "GND_2") (pintype "passive"))
      (node (ref "X1") (pin "4") (pinfunction "GND_4") (pintype "passive"))
    )
    (net (code "39") (name "Net-(ANT1-FEED)") (class "Default")
      (node (ref "ANT1") (pin "1") (pinfunction "FEED_1") (pintype "passive"))
      (node (ref "C9") (pin "2") (pinfunction "2_2") (pintype "passive"))
      (node (ref "L1") (pin "2") (pinfunction "2_2") (pintype "passive"))
    )
    (net (code "40") (name "Net-(D4-1)") (class "Default")
      (node (ref "D4") (pin "A") (pinfunction "1_A") (pintype "passive"))
      (node (ref "R14") (pin "1") (pinfunction "1_1") (pintype "passive"))
    )
    (net (code "41") (name "Net-(J1-CC1)") (class "Default")
      (node (ref "J1") (pin "A5") (pinfunction "CC1_A5") (pintype "bidirectional"))
      (node (ref "R1") (pin "2") (pinfunction "2_2") (pintype "passive"))
    )
    (net (code "42") (name "Net-(J1-CC2)") (class "Default")
      (node (ref "J1") (pin "B5") (pinfunction "CC2_B5") (pintype "bidirectional"))
      (node (ref "R2") (pin "2") (pinfunction "2_2") (pintype "passive"))
    )
    (net (code "43") (name "Net-(Q1A-D)") (class "Default")
      (node (ref "Q1") (pin "5") (pinfunction "G_5") (pintype "passive"))
      (node (ref "Q1") (pin "6") (pinfunction "D_6") (pintype "passive"))
      (node (ref "R3") (pin "1") (pinfunction "1_1") (pintype "passive"))
    )
    (net (code "44") (name "Net-(Q1B-D)") (class "Default")
      (node (ref "Q1") (pin "3") (pinfunction "D_3") (pintype "passive"))
      (node (ref "R6") (pin "2") (pinfunction "2_2") (pintype "passive"))
    )
    (net (code "45") (name "Net-(Q2A-G)") (class "Default")
      (node (ref "Q2") (pin "2") (pinfunction "G_2") (pintype "passive"))
      (node (ref "Q2") (pin "5") (pinfunction "G_5") (pintype "passive"))
      (node (ref "R16") (pin "2") (pinfunction "2_2") (pintype "passive"))
      (node (ref "SW1") (pin "1") (pinfunction "1_1") (pintype "passive"))
      (node (ref "SW1") (pin "2") (pinfunction "2_2") (pintype "passive"))
    )
    (net (code "46") (name "Net-(U4A-LNA_IN)") (class "Default")
      (node (ref "C8") (pin "2") (pinfunction "2_2") (pintype "passive"))
      (node (ref "L1") (pin "1") (pinfunction "1_1") (pintype "passive"))
      (node (ref "U4") (pin "1") (pinfunction "LNA_IN_1") (pintype "bidirectional"))
    )
    (net (code "47") (name "Net-(U4B-XTAL_N)") (class "Default")
      (node (ref "C15") (pin "1") (pinfunction "1_1") (pintype "passive"))
      (node (ref "U4") (pin "53") (pinfunction "XTAL_N_53") (pintype "output"))
      (node (ref "X1") (pin "1") (pinfunction "IN_1") (pintype "passive"))
    )
    (net (code "48") (name "Net-(U4B-XTAL_P)") (class "Default")
      (node (ref "C18") (pin "1") (pinfunction "1_1") (pintype "passive"))
      (node (ref "U4") (pin "54") (pinfunction "XTAL_P_54") (pintype "input"))
      (node (ref "X1") (pin "3") (pinfunction "OUT_3") (pintype "passive"))
    )
    (net (code "49") (name "unconnected-(J1-SBU1-PadA8)") (class "Default")
      (node (ref "J1") (pin "A8") (pinfunction "SBU1_A8") (pintype "bidirectional+no_connect"))
    )
    (net (code "50") (name "unconnected-(U4A-GPIO3-Pad8)") (class "Default")
      (node (ref "U4") (pin "8") (pinfunction "GPIO3_8") (pintype "bidirectional+no_connect"))
    )
    (net (code "51") (name "unconnected-(U4A-GPIO5-Pad10)") (class "Default")
      (node (ref "U4") (pin "10") (pinfunction "GPIO5_10") (pintype "bidirectional+no_connect"))
    )
    (net (code "52") (name "unconnected-(U4A-GPIO6-Pad11)") (class "Default")
      (node (ref "U4") (pin "11") (pinfunction "GPIO6_11") (pintype "bidirectional+no_connect"))
    )
    (net (code "53") (name "unconnected-(U4A-GPIO8-Pad13)") (class "Default")
      (node (ref "U4") (pin "13") (pinfunction "GPIO8_13") (pintype "bidirectional+no_connect"))
    )
    (net (code "54") (name "unconnected-(U4A-GPIO9-Pad14)") (class "Default")
      (node (ref "U4") (pin "14") (pinfunction "GPIO9_14") (pintype "bidirectional+no_connect"))
    )
    (net (code "55") (name "unconnected-(U4A-GPIO21-Pad27)") (class "Default")
      (node (ref "U4") (pin "27") (pinfunction "GPIO21_27") (pintype "bidirectional+no_connect"))
    )
    (net (code "56") (name "unconnected-(U4A-GPIO33-Pad38)") (class "Default")
      (node (ref "U4") (pin "38") (pinfunction "GPIO33_38") (pintype "bidirectional+no_connect"))
    )
    (net (code "57") (name "unconnected-(U4A-GPIO34-Pad39)") (class "Default")
      (node (ref "U4") (pin "39") (pinfunction "GPIO34_39") (pintype "bidirectional+no_connect"))
    )
    (net (code "58") (name "unconnected-(U4A-GPIO45-Pad51)") (class "Default")
      (node (ref "U4") (pin "51") (pinfunction "GPIO45_51") (pintype "bidirectional+no_connect"))
    )
    (net (code "59") (name "unconnected-(U4A-GPIO46-Pad52)") (class "Default")
      (node (ref "U4") (pin "52") (pinfunction "GPIO46_52") (pintype "bidirectional+no_connect"))
    )
    (net (code "60") (name "unconnected-(U4A-SPICLK-Pad33)") (class "Default")
      (node (ref "U4") (pin "33") (pinfunction "SPICLK_33") (pintype "bidirectional+no_connect"))
    )
    (net (code "61") (name "unconnected-(U4A-SPICLK_N-Pad36)") (class "Default")
      (node (ref "U4") (pin "36") (pinfunction "SPICLK_N_36") (pintype "bidirectional+no_connect"))
    )
    (net (code "62") (name "unconnected-(U4A-SPICLK_P-Pad37)") (class "Default")
      (node (ref "U4") (pin "37") (pinfunction "SPICLK_P_37") (pintype "bidirectional+no_connect"))
    )
    (net (code "63") (name "unconnected-(U4A-SPICS0-Pad32)") (class "Default")
      (node (ref "U4") (pin "32") (pinfunction "SPICS0_32") (pintype "bidirectional+no_connect"))
    )
    (net (code "64") (name "unconnected-(U4A-SPICS1-Pad28)") (class "Default")
      (node (ref "U4") (pin "28") (pinfunction "SPICS1_28") (pintype "bidirectional+no_connect"))
    )
    (net (code "65") (name "unconnected-(U4A-SPID-Pad35)") (class "Default")
      (node (ref "U4") (pin "35") (pinfunction "SPID_35") (pintype "bidirectional+no_connect"))
    )
    (net (code "66") (name "unconnected-(U4A-SPIHD-Pad30)") (class "Default")
      (node (ref "U4") (pin "30") (pinfunction "SPIHD_30") (pintype "bidirectional+no_connect"))
    )
    (net (code "67") (name "unconnected-(U4A-SPIQ-Pad34)") (class "Default")
      (node (ref "U4") (pin "34") (pinfunction "SPIQ_34") (pintype "bidirectional+no_connect"))
    )
    (net (code "68") (name "unconnected-(U4A-SPIWP-Pad31)") (class "Default")
      (node (ref "U4") (pin "31") (pinfunction "SPIWP_31") (pintype "bidirectional+no_connect"))
    )
    (net (code "69") (name "unconnected-(U4B-XTAL_32K_N-Pad22)") (class "Default")
      (node (ref "U4") (pin "22") (pinfunction "XTAL_32K_N_22") (pintype "bidirectional+no_connect"))
    )
    (net (code "70") (name "unconnected-(U4B-XTAL_32K_P-Pad21)") (class "Default")
      (node (ref "U4") (pin "21") (pinfunction "XTAL_32K_P_21") (pintype "bidirectional+no_connect"))
    )
  )
)
